# Own_LiPoC1_v1_0_Final.net
KiCad netlist of a schematic drawn in EAGLE
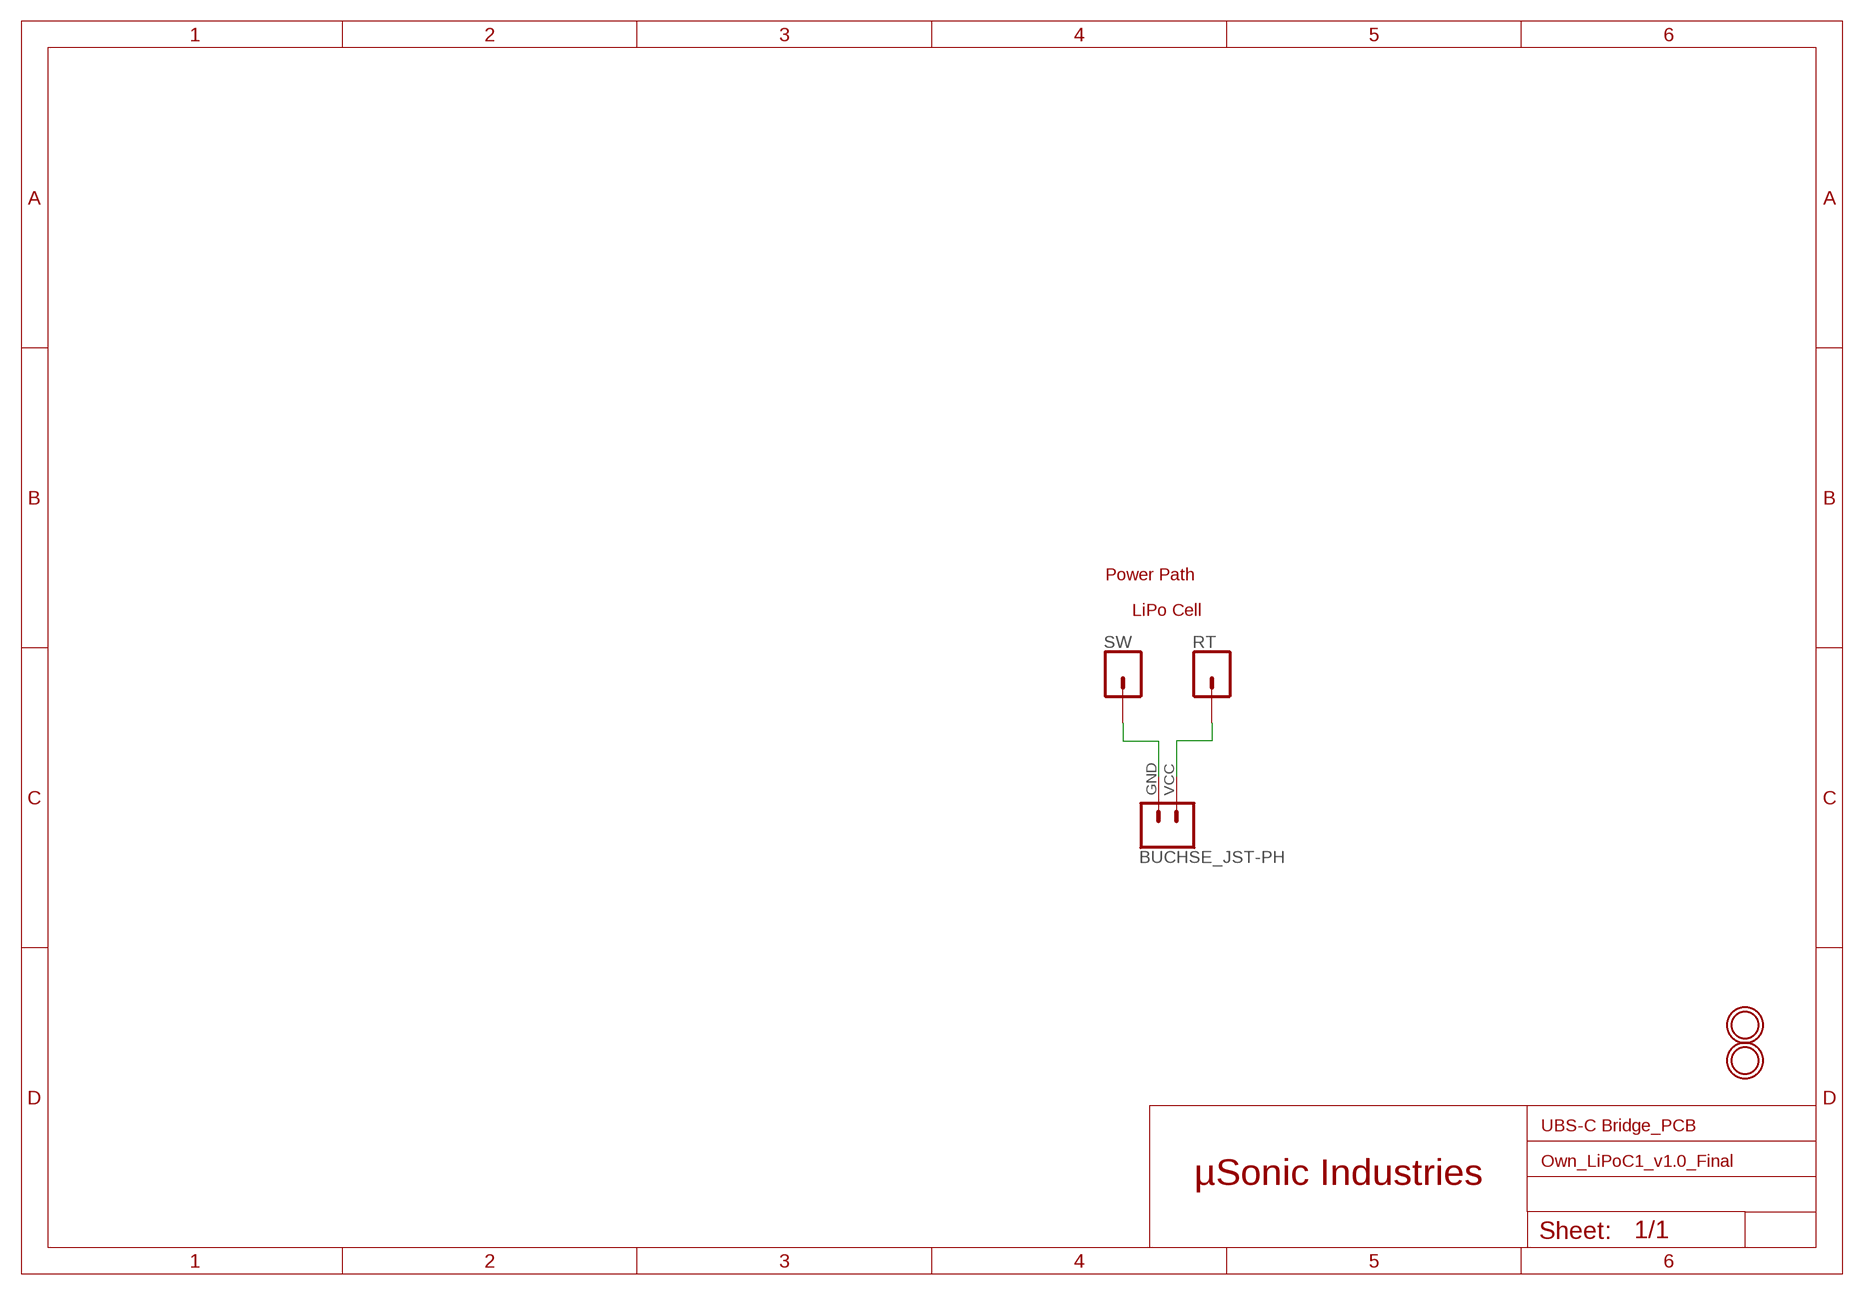
[diagram p0: schematic, sheet 1]

(export (version "E")
  (design (tool "Eeschema 10.0.6"))
  (components
    (comp (ref "BUCHSE_JST-PH")
      (value "CONN_024UCON-15767")
      (footprint "eagle-import:JST-2-SMD-VERT")
      (libsource (lib "eagle-import") (part "CONN_024UCON-15767"))
    )
    (comp (ref "RT")
      (value "CONN_01OFFSET")
      (footprint "eagle-import:1X01_OFFSET")
      (libsource (lib "eagle-import") (part "CONN_01OFFSET"))
    )
    (comp (ref "SW")
      (value "CONN_01OFFSET")
      (footprint "eagle-import:1X01_OFFSET")
      (libsource (lib "eagle-import") (part "CONN_01OFFSET"))
    )
    (comp (ref "U$2")
      (value "MOUNTINGHOLE2.5")
      (footprint "eagle-import:MOUNTINGHOLE_2.5_PLATED")
      (libsource (lib "eagle-import") (part "MOUNTINGHOLE2.5"))
    )
    (comp (ref "U$10")
      (value "MOUNTINGHOLE2.5")
      (footprint "eagle-import:MOUNTINGHOLE_2.5_PLATED")
      (libsource (lib "eagle-import") (part "MOUNTINGHOLE2.5"))
    )
  )
  (nets
    (net (code "1") (name "Net-(BUCHSE_JST-PH-1)") (class "Default")
      (node (ref "BUCHSE_JST-PH") (pin "GND") (pinfunction "1_GND") (pintype "passive"))
      (node (ref "SW") (pin "1") (pinfunction "1_1") (pintype "passive"))
    )
    (net (code "2") (name "Net-(BUCHSE_JST-PH-2)") (class "Default")
      (node (ref "BUCHSE_JST-PH") (pin "VCC") (pinfunction "2_VCC") (pintype "passive"))
      (node (ref "RT") (pin "1") (pinfunction "1_1") (pintype "passive"))
    )
  )
)
